# Power.net
KiCad netlist of a schematic drawn in Altium Designer
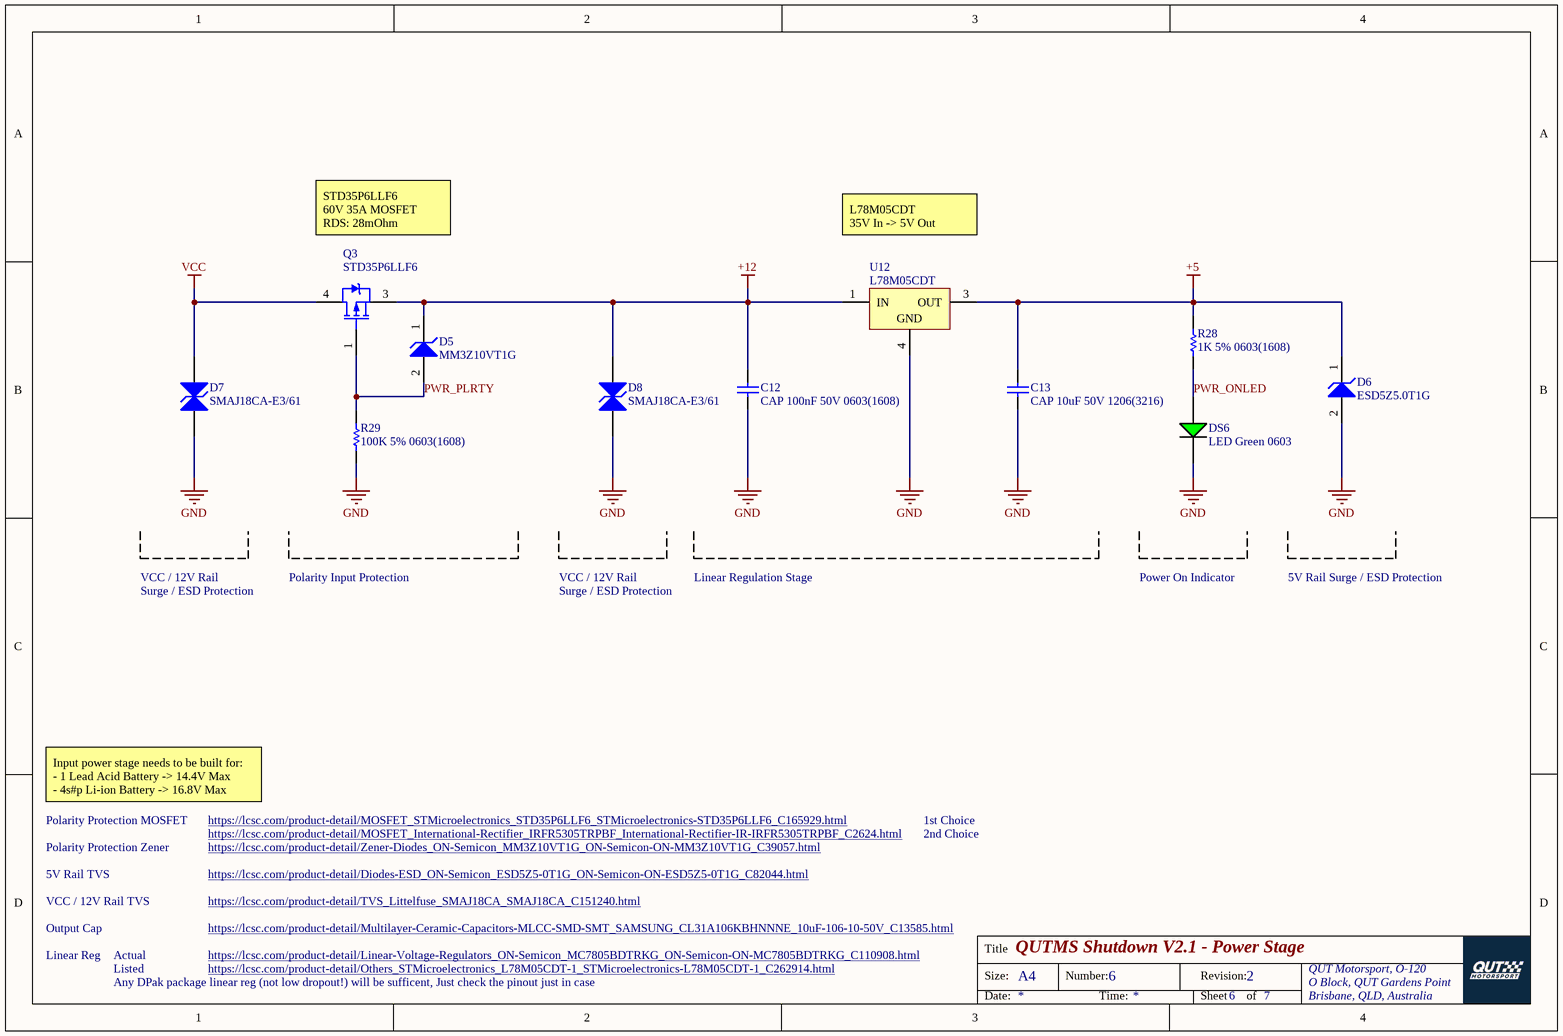
[diagram p0: Power.SchDoc]

(export (version "E")
  (design (tool "Eeschema 10.0.6"))
  (components
    (comp (ref "C12")
      (value "CAP 100nF 50V 0603(1608)")
      (footprint "CAPC0603(1608)100_N")
      (description "CAP 100nF 50V ±5% 0603 (1608 Metric) Thickness 1mm SMD")
      (fields (field (name "TOLERANCE") "Â±5%"))
      (libsource (lib "Altium Content Vault") (part "CAP"))
    )
    (comp (ref "C13")
      (value "CAP 10uF 50V 1206(3216)")
      (footprint "CAPC1206(3216)190_N")
      (description "CAP 10uF 50V ±10% 1206 (3216 Metric) Thickness 1.9mm SMD")
      (fields (field (name "TOLERANCE") "Â±10%"))
      (libsource (lib "Altium Content Vault") (part "CAP"))
    )
    (comp (ref "D5")
      (value "MM3Z10VT1G")
      (footprint "ONSC-SOD-323-2-477-02_V")
      (description "Zener Voltage Regulator, 300 mW, 2-Pin SOD-323, Pb-Free, Tape and Reel")
      (fields (field (name "MANUFACTURER") "On Semiconductor"))
      (libsource (lib "Altium Content Vault") (part "ONSC-K1A2-2"))
    )
    (comp (ref "D6")
      (value "ESD5Z5.0T1G")
      (footprint "ONSC-SOD-523-2-502-01_V")
      (fields (field (name "MANUFACTURER") "On Semiconductor"))
      (libsource (lib "Altium Content Vault") (part "ONSC-K1A2-2"))
    )
    (comp (ref "D7")
      (value "SMAJ18CA-E3/61")
      (footprint "VISH-DO-214AC-2_N")
      (fields (field (name "MANUFACTURER") "Vishay Semiconductor"))
      (libsource (lib "Altium Content Vault") (part "VISH-A1A2-2"))
    )
    (comp (ref "D8")
      (value "SMAJ18CA-E3/61")
      (footprint "VISH-DO-214AC-2_N")
      (fields (field (name "MANUFACTURER") "Vishay Semiconductor"))
      (libsource (lib "Altium Content Vault") (part "VISH-A1A2-2"))
    )
    (comp (ref "DS6")
      (value "LED Green 0603")
      (footprint "LED GREEN 0603")
      (libsource (lib "QUTMS_LEDLibrary") (part "LED GREEN 0603"))
    )
    (comp (ref "Q3")
      (value "STD35P6LLF6")
      (footprint "ONSC-DPAK-3-369C-01_V")
      (description "Power MOSFET, -60 V, -12 A, P-Channel, 3-Pin DPAK, Pb-Free, Tape and Reel")
      (fields (field (name "MANUFACTURER") "On Semiconductor") (field (name "PARTNUMBER") "NTD2955T4G"))
      (libsource (lib "Altium Content Vault") (part "ONSC-PMOS-G1S3D4-3_B"))
    )
    (comp (ref "R28")
      (value "1K 5% 0603(1608)")
      (footprint "RESC0603(1608)_N")
      (description "1K 0.1W 5% 0603 (1608 Metric)  SMD")
      (fields (field (name "TOLERANCE") "5 %") (field (name "POWER") "0.1 W"))
      (libsource (lib "Altium Content Vault") (part "RES"))
    )
    (comp (ref "R29")
      (value "100K 5% 0603(1608)")
      (footprint "RESC0603(1608)_N")
      (description "100K 0.1W 5% 0603 (1608 Metric)  SMD")
      (fields (field (name "TOLERANCE") "5 %") (field (name "POWER") "0.1 W"))
      (libsource (lib "Altium Content Vault") (part "RES"))
    )
    (comp (ref "U12")
      (value "L78M05CDT")
      (footprint "STM-TO252-3_A_V")
      (description "Precision Regulator, 0.5 A, 5 V Output, 0 to 150 degC, 3-Pin DPAK (TO252), RoHS, Tube")
      (fields (field (name "MANUFACTURER") "STMicroelectronics"))
      (libsource (lib "Altium Content Vault") (part "STM-L78M05-TO252-3"))
    )
  )
  (nets
    (net (code "1") (name "+5") (class "Default")
      (node (ref "C13") (pin "2") (pinfunction "2_2") (pintype "passive"))
      (node (ref "D6") (pin "1") (pinfunction "K_1") (pintype "passive"))
      (node (ref "R28") (pin "2") (pinfunction "2_2") (pintype "passive"))
      (node (ref "U12") (pin "3") (pinfunction "OUT_3") (pintype "power_in"))
    )
    (net (code "2") (name "+12") (class "Default")
      (node (ref "C12") (pin "2") (pinfunction "2_2") (pintype "passive"))
      (node (ref "D5") (pin "1") (pinfunction "K_1") (pintype "passive"))
      (node (ref "D8") (pin "2") (pinfunction "A2_2") (pintype "passive"))
      (node (ref "Q3") (pin "3") (pinfunction "S_3") (pintype "passive"))
      (node (ref "U12") (pin "1") (pinfunction "IN_1") (pintype "power_in"))
    )
    (net (code "3") (name "/PWR_ONLED") (class "Default")
      (node (ref "DS6") (pin "1") (pinfunction "A_1") (pintype "passive"))
      (node (ref "R28") (pin "1") (pinfunction "1_1") (pintype "passive"))
    )
    (net (code "4") (name "/PWR_PLRTY") (class "Default")
      (node (ref "D5") (pin "2") (pinfunction "A_2") (pintype "passive"))
      (node (ref "Q3") (pin "1") (pinfunction "G_1") (pintype "passive"))
      (node (ref "R29") (pin "2") (pinfunction "2_2") (pintype "passive"))
    )
    (net (code "5") (name "GND") (class "Default")
      (node (ref "C12") (pin "1") (pinfunction "1_1") (pintype "passive"))
      (node (ref "C13") (pin "1") (pinfunction "1_1") (pintype "passive"))
      (node (ref "D6") (pin "2") (pinfunction "A_2") (pintype "passive"))
      (node (ref "D7") (pin "1") (pinfunction "A1_1") (pintype "passive"))
      (node (ref "D8") (pin "1") (pinfunction "A1_1") (pintype "passive"))
      (node (ref "DS6") (pin "2") (pinfunction "C_2") (pintype "passive"))
      (node (ref "R29") (pin "1") (pinfunction "1_1") (pintype "passive"))
      (node (ref "U12") (pin "4") (pinfunction "GND_4") (pintype "power_in"))
    )
    (net (code "6") (name "VCC") (class "Default")
      (node (ref "D7") (pin "2") (pinfunction "A2_2") (pintype "passive"))
      (node (ref "Q3") (pin "4") (pinfunction "D_4") (pintype "passive"))
    )
  )
)
